# Stopwatch.net
KiCad netlist of a schematic drawn in EAGLE
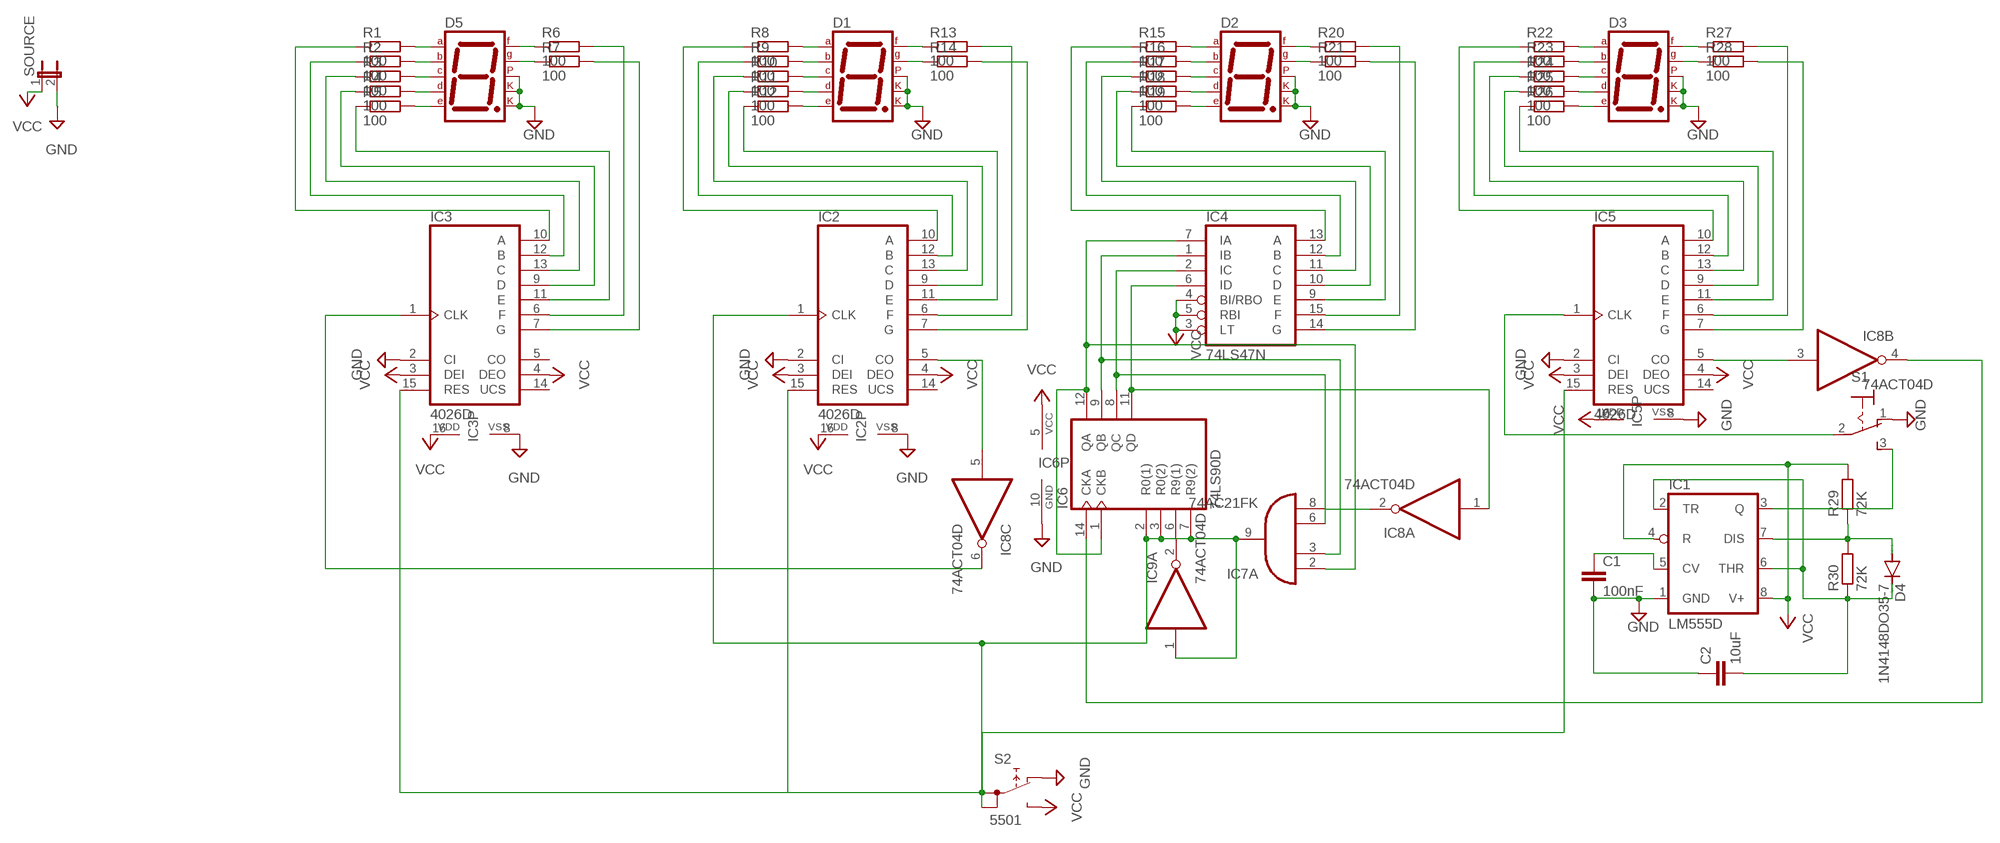
[diagram p0: schematic, sheet 1]

(export (version "E")
  (design (tool "Eeschema 10.0.6"))
  (components
    (comp (ref "C1")
      (value "100nF")
      (footprint "eagle-import:C2.5-2")
      (libsource (lib "eagle-import") (part "C2.5/2"))
    )
    (comp (ref "C2")
      (value "10uF")
      (footprint "eagle-import:C2.5-2")
      (libsource (lib "eagle-import") (part "C2.5/2"))
    )
    (comp (ref "D1")
      (value "7SEG-CK")
      (footprint "eagle-import:7SEG-13")
      (libsource (lib "eagle-import") (part "7SEG-CK"))
    )
    (comp (ref "D2")
      (value "7SEG-CK")
      (footprint "eagle-import:7SEG-13")
      (libsource (lib "eagle-import") (part "7SEG-CK"))
    )
    (comp (ref "D3")
      (value "7SEG-CK")
      (footprint "eagle-import:7SEG-13")
      (libsource (lib "eagle-import") (part "7SEG-CK"))
    )
    (comp (ref "D4")
      (value "1N4148DO35-7")
      (footprint "eagle-import:DO35-7")
      (libsource (lib "eagle-import") (part "1N4148DO35-7"))
    )
    (comp (ref "D5")
      (value "7SEG-CK")
      (footprint "eagle-import:7SEG-13")
      (libsource (lib "eagle-import") (part "7SEG-CK"))
    )
    (comp (ref "IC1")
      (value "LM555D")
      (footprint "eagle-import:SO08")
      (libsource (lib "eagle-import") (part "555DLM"))
    )
    (comp (ref "IC2")
      (value "4026D")
      (footprint "eagle-import:SO16")
      (libsource (lib "eagle-import") (part "4026D"))
    )
    (comp (ref "IC3")
      (value "4026D")
      (footprint "eagle-import:SO16")
      (libsource (lib "eagle-import") (part "4026D"))
    )
    (comp (ref "IC4")
      (value "74LS47N")
      (footprint "eagle-import:DIL16")
      (libsource (lib "eagle-import") (part "7447NLS"))
    )
    (comp (ref "IC5")
      (value "4026D")
      (footprint "eagle-import:SO16")
      (libsource (lib "eagle-import") (part "4026D"))
    )
    (comp (ref "IC6")
      (value "74LS90D")
      (footprint "eagle-import:SO14")
      (libsource (lib "eagle-import") (part "7490DLS"))
    )
    (comp (ref "IC7")
      (value "74AC21FK")
      (footprint "eagle-import:LCC20")
      (libsource (lib "eagle-import") (part "7421FKAC"))
    )
    (comp (ref "IC8")
      (value "74ACT04D")
      (footprint "eagle-import:SO14")
      (libsource (lib "eagle-import") (part "7404DACT"))
    )
    (comp (ref "IC9")
      (value "74ACT04D")
      (footprint "eagle-import:SO14")
      (libsource (lib "eagle-import") (part "7404DACT"))
    )
    (comp (ref "R1")
      (value "100")
      (footprint "eagle-import:R0805")
      (libsource (lib "eagle-import") (part "R-EU_R0805"))
    )
    (comp (ref "R2")
      (value "100")
      (footprint "eagle-import:R0805")
      (libsource (lib "eagle-import") (part "R-EU_R0805"))
    )
    (comp (ref "R3")
      (value "100")
      (footprint "eagle-import:R0805")
      (libsource (lib "eagle-import") (part "R-EU_R0805"))
    )
    (comp (ref "R4")
      (value "100")
      (footprint "eagle-import:R0805")
      (libsource (lib "eagle-import") (part "R-EU_R0805"))
    )
    (comp (ref "R5")
      (value "100")
      (footprint "eagle-import:R0805")
      (libsource (lib "eagle-import") (part "R-EU_R0805"))
    )
    (comp (ref "R6")
      (value "100")
      (footprint "eagle-import:R0805")
      (libsource (lib "eagle-import") (part "R-EU_R0805"))
    )
    (comp (ref "R7")
      (value "100")
      (footprint "eagle-import:R0805")
      (libsource (lib "eagle-import") (part "R-EU_R0805"))
    )
    (comp (ref "R8")
      (value "100")
      (footprint "eagle-import:R0805")
      (libsource (lib "eagle-import") (part "R-EU_R0805"))
    )
    (comp (ref "R9")
      (value "100")
      (footprint "eagle-import:R0805")
      (libsource (lib "eagle-import") (part "R-EU_R0805"))
    )
    (comp (ref "R10")
      (value "100")
      (footprint "eagle-import:R0805")
      (libsource (lib "eagle-import") (part "R-EU_R0805"))
    )
    (comp (ref "R11")
      (value "100")
      (footprint "eagle-import:R0805")
      (libsource (lib "eagle-import") (part "R-EU_R0805"))
    )
    (comp (ref "R12")
      (value "100")
      (footprint "eagle-import:R0805")
      (libsource (lib "eagle-import") (part "R-EU_R0805"))
    )
    (comp (ref "R13")
      (value "100")
      (footprint "eagle-import:R0805")
      (libsource (lib "eagle-import") (part "R-EU_R0805"))
    )
    (comp (ref "R14")
      (value "100")
      (footprint "eagle-import:R0805")
      (libsource (lib "eagle-import") (part "R-EU_R0805"))
    )
    (comp (ref "R15")
      (value "100")
      (footprint "eagle-import:R0805")
      (libsource (lib "eagle-import") (part "R-EU_R0805"))
    )
    (comp (ref "R16")
      (value "100")
      (footprint "eagle-import:R0805")
      (libsource (lib "eagle-import") (part "R-EU_R0805"))
    )
    (comp (ref "R17")
      (value "100")
      (footprint "eagle-import:R0805")
      (libsource (lib "eagle-import") (part "R-EU_R0805"))
    )
    (comp (ref "R18")
      (value "100")
      (footprint "eagle-import:R0805")
      (libsource (lib "eagle-import") (part "R-EU_R0805"))
    )
    (comp (ref "R19")
      (value "100")
      (footprint "eagle-import:R0805")
      (libsource (lib "eagle-import") (part "R-EU_R0805"))
    )
    (comp (ref "R20")
      (value "100")
      (footprint "eagle-import:R0805")
      (libsource (lib "eagle-import") (part "R-EU_R0805"))
    )
    (comp (ref "R21")
      (value "100")
      (footprint "eagle-import:R0805")
      (libsource (lib "eagle-import") (part "R-EU_R0805"))
    )
    (comp (ref "R22")
      (value "100")
      (footprint "eagle-import:R0805")
      (libsource (lib "eagle-import") (part "R-EU_R0805"))
    )
    (comp (ref "R23")
      (value "100")
      (footprint "eagle-import:R0805")
      (libsource (lib "eagle-import") (part "R-EU_R0805"))
    )
    (comp (ref "R24")
      (value "100")
      (footprint "eagle-import:R0805")
      (libsource (lib "eagle-import") (part "R-EU_R0805"))
    )
    (comp (ref "R25")
      (value "100")
      (footprint "eagle-import:R0805")
      (libsource (lib "eagle-import") (part "R-EU_R0805"))
    )
    (comp (ref "R26")
      (value "100")
      (footprint "eagle-import:R0805")
      (libsource (lib "eagle-import") (part "R-EU_R0805"))
    )
    (comp (ref "R27")
      (value "100")
      (footprint "eagle-import:R0805")
      (libsource (lib "eagle-import") (part "R-EU_R0805"))
    )
    (comp (ref "R28")
      (value "100")
      (footprint "eagle-import:R0805")
      (libsource (lib "eagle-import") (part "R-EU_R0805"))
    )
    (comp (ref "R29")
      (value "72K")
      (footprint "eagle-import:R0805")
      (libsource (lib "eagle-import") (part "R-EU_R0805"))
    )
    (comp (ref "R30")
      (value "72K")
      (footprint "eagle-import:R0805")
      (libsource (lib "eagle-import") (part "R-EU_R0805"))
    )
    (comp (ref "S1")
      (value "320-916")
      (footprint "eagle-import:320-916")
      (libsource (lib "eagle-import") (part "320-916"))
    )
    (comp (ref "S2")
      (value "5501")
      (footprint "eagle-import:5501")
      (libsource (lib "eagle-import") (part "55?01"))
    )
    (comp (ref "SOURCE")
      (value "JP1E")
      (footprint "eagle-import:JP1")
      (libsource (lib "eagle-import") (part "JP1E"))
    )
  )
  (nets
    (net (code "1") (name "GND") (class "Default")
      (node (ref "C1") (pin "2") (pinfunction "2_2") (pintype "passive"))
      (node (ref "C2") (pin "1") (pinfunction "1_1") (pintype "passive"))
      (node (ref "D1") (pin "3") (pinfunction "CK1_3") (pintype "passive"))
      (node (ref "D1") (pin "5") (pinfunction "DP_5") (pintype "passive"))
      (node (ref "D1") (pin "8") (pinfunction "CK2_8") (pintype "passive"))
      (node (ref "D2") (pin "3") (pinfunction "CK1_3") (pintype "passive"))
      (node (ref "D2") (pin "5") (pinfunction "DP_5") (pintype "passive"))
      (node (ref "D2") (pin "8") (pinfunction "CK2_8") (pintype "passive"))
      (node (ref "D3") (pin "3") (pinfunction "CK1_3") (pintype "passive"))
      (node (ref "D3") (pin "5") (pinfunction "DP_5") (pintype "passive"))
      (node (ref "D3") (pin "8") (pinfunction "CK2_8") (pintype "passive"))
      (node (ref "D5") (pin "3") (pinfunction "CK1_3") (pintype "passive"))
      (node (ref "D5") (pin "5") (pinfunction "DP_5") (pintype "passive"))
      (node (ref "D5") (pin "8") (pinfunction "CK2_8") (pintype "passive"))
      (node (ref "IC1") (pin "1") (pinfunction "GND_1") (pintype "power_in"))
      (node (ref "IC2") (pin "2") (pinfunction "CI_2") (pintype "input"))
      (node (ref "IC2") (pin "8") (pinfunction "VSS_8") (pintype "power_in"))
      (node (ref "IC3") (pin "2") (pinfunction "CI_2") (pintype "input"))
      (node (ref "IC3") (pin "8") (pinfunction "VSS_8") (pintype "power_in"))
      (node (ref "IC5") (pin "2") (pinfunction "CI_2") (pintype "input"))
      (node (ref "IC5") (pin "8") (pinfunction "VSS_8") (pintype "power_in"))
      (node (ref "IC6") (pin "10") (pinfunction "GND_10") (pintype "power_in"))
      (node (ref "S1") (pin "1") (pinfunction "O_1") (pintype "passive"))
      (node (ref "S2") (pin "NC") (pinfunction "NC_NC") (pintype "passive"))
      (node (ref "SOURCE") (pin "2") (pinfunction "2_2") (pintype "passive"))
    )
    (net (code "2") (name "Net-(D1-A)") (class "Default")
      (node (ref "D1") (pin "7") (pinfunction "A_7") (pintype "passive"))
      (node (ref "R8") (pin "2") (pinfunction "2_2") (pintype "passive"))
    )
    (net (code "3") (name "Net-(D1-B)") (class "Default")
      (node (ref "D1") (pin "6") (pinfunction "B_6") (pintype "passive"))
      (node (ref "R9") (pin "2") (pinfunction "2_2") (pintype "passive"))
    )
    (net (code "4") (name "Net-(D1-C)") (class "Default")
      (node (ref "D1") (pin "4") (pinfunction "C_4") (pintype "passive"))
      (node (ref "R10") (pin "2") (pinfunction "2_2") (pintype "passive"))
    )
    (net (code "5") (name "Net-(D1-D)") (class "Default")
      (node (ref "D1") (pin "2") (pinfunction "D_2") (pintype "passive"))
      (node (ref "R11") (pin "2") (pinfunction "2_2") (pintype "passive"))
    )
    (net (code "6") (name "Net-(D1-E)") (class "Default")
      (node (ref "D1") (pin "1") (pinfunction "E_1") (pintype "passive"))
      (node (ref "R12") (pin "2") (pinfunction "2_2") (pintype "passive"))
    )
    (net (code "7") (name "Net-(D1-F)") (class "Default")
      (node (ref "D1") (pin "9") (pinfunction "F_9") (pintype "passive"))
      (node (ref "R13") (pin "1") (pinfunction "1_1") (pintype "passive"))
    )
    (net (code "8") (name "Net-(D1-G)") (class "Default")
      (node (ref "D1") (pin "10") (pinfunction "G_10") (pintype "passive"))
      (node (ref "R14") (pin "1") (pinfunction "1_1") (pintype "passive"))
    )
    (net (code "9") (name "Net-(D2-A)") (class "Default")
      (node (ref "D2") (pin "7") (pinfunction "A_7") (pintype "passive"))
      (node (ref "R15") (pin "2") (pinfunction "2_2") (pintype "passive"))
    )
    (net (code "10") (name "Net-(D2-B)") (class "Default")
      (node (ref "D2") (pin "6") (pinfunction "B_6") (pintype "passive"))
      (node (ref "R16") (pin "2") (pinfunction "2_2") (pintype "passive"))
    )
    (net (code "11") (name "Net-(D2-C)") (class "Default")
      (node (ref "D2") (pin "4") (pinfunction "C_4") (pintype "passive"))
      (node (ref "R17") (pin "2") (pinfunction "2_2") (pintype "passive"))
    )
    (net (code "12") (name "Net-(D2-D)") (class "Default")
      (node (ref "D2") (pin "2") (pinfunction "D_2") (pintype "passive"))
      (node (ref "R18") (pin "2") (pinfunction "2_2") (pintype "passive"))
    )
    (net (code "13") (name "Net-(D2-E)") (class "Default")
      (node (ref "D2") (pin "1") (pinfunction "E_1") (pintype "passive"))
      (node (ref "R19") (pin "2") (pinfunction "2_2") (pintype "passive"))
    )
    (net (code "14") (name "Net-(D2-F)") (class "Default")
      (node (ref "D2") (pin "9") (pinfunction "F_9") (pintype "passive"))
      (node (ref "R20") (pin "1") (pinfunction "1_1") (pintype "passive"))
    )
    (net (code "15") (name "Net-(D2-G)") (class "Default")
      (node (ref "D2") (pin "10") (pinfunction "G_10") (pintype "passive"))
      (node (ref "R21") (pin "1") (pinfunction "1_1") (pintype "passive"))
    )
    (net (code "16") (name "Net-(D3-A)") (class "Default")
      (node (ref "D3") (pin "7") (pinfunction "A_7") (pintype "passive"))
      (node (ref "R22") (pin "2") (pinfunction "2_2") (pintype "passive"))
    )
    (net (code "17") (name "Net-(D3-B)") (class "Default")
      (node (ref "D3") (pin "6") (pinfunction "B_6") (pintype "passive"))
      (node (ref "R23") (pin "2") (pinfunction "2_2") (pintype "passive"))
    )
    (net (code "18") (name "Net-(D3-C)") (class "Default")
      (node (ref "D3") (pin "4") (pinfunction "C_4") (pintype "passive"))
      (node (ref "R24") (pin "2") (pinfunction "2_2") (pintype "passive"))
    )
    (net (code "19") (name "Net-(D3-D)") (class "Default")
      (node (ref "D3") (pin "2") (pinfunction "D_2") (pintype "passive"))
      (node (ref "R25") (pin "2") (pinfunction "2_2") (pintype "passive"))
    )
    (net (code "20") (name "Net-(D3-E)") (class "Default")
      (node (ref "D3") (pin "1") (pinfunction "E_1") (pintype "passive"))
      (node (ref "R26") (pin "2") (pinfunction "2_2") (pintype "passive"))
    )
    (net (code "21") (name "Net-(D3-F)") (class "Default")
      (node (ref "D3") (pin "9") (pinfunction "F_9") (pintype "passive"))
      (node (ref "R27") (pin "1") (pinfunction "1_1") (pintype "passive"))
    )
    (net (code "22") (name "Net-(D3-G)") (class "Default")
      (node (ref "D3") (pin "10") (pinfunction "G_10") (pintype "passive"))
      (node (ref "R28") (pin "1") (pinfunction "1_1") (pintype "passive"))
    )
    (net (code "23") (name "Net-(D5-A)") (class "Default")
      (node (ref "D5") (pin "7") (pinfunction "A_7") (pintype "passive"))
      (node (ref "R1") (pin "2") (pinfunction "2_2") (pintype "passive"))
    )
    (net (code "24") (name "Net-(D5-B)") (class "Default")
      (node (ref "D5") (pin "6") (pinfunction "B_6") (pintype "passive"))
      (node (ref "R2") (pin "2") (pinfunction "2_2") (pintype "passive"))
    )
    (net (code "25") (name "Net-(D5-C)") (class "Default")
      (node (ref "D5") (pin "4") (pinfunction "C_4") (pintype "passive"))
      (node (ref "R3") (pin "2") (pinfunction "2_2") (pintype "passive"))
    )
    (net (code "26") (name "Net-(D5-D)") (class "Default")
      (node (ref "D5") (pin "2") (pinfunction "D_2") (pintype "passive"))
      (node (ref "R4") (pin "2") (pinfunction "2_2") (pintype "passive"))
    )
    (net (code "27") (name "Net-(D5-E)") (class "Default")
      (node (ref "D5") (pin "1") (pinfunction "E_1") (pintype "passive"))
      (node (ref "R5") (pin "2") (pinfunction "2_2") (pintype "passive"))
    )
    (net (code "28") (name "Net-(D5-F)") (class "Default")
      (node (ref "D5") (pin "9") (pinfunction "F_9") (pintype "passive"))
      (node (ref "R6") (pin "1") (pinfunction "1_1") (pintype "passive"))
    )
    (net (code "29") (name "Net-(D5-G)") (class "Default")
      (node (ref "D5") (pin "10") (pinfunction "G_10") (pintype "passive"))
      (node (ref "R7") (pin "1") (pinfunction "1_1") (pintype "passive"))
    )
    (net (code "30") (name "Net-(IC1-CV)") (class "Default")
      (node (ref "C1") (pin "1") (pinfunction "1_1") (pintype "passive"))
      (node (ref "IC1") (pin "5") (pinfunction "CV_5") (pintype "input"))
    )
    (net (code "31") (name "Net-(IC1-DIS)") (class "Default")
      (node (ref "D4") (pin "A") (pinfunction "A_A") (pintype "passive"))
      (node (ref "IC1") (pin "7") (pinfunction "DIS_7") (pintype "input"))
      (node (ref "R29") (pin "1") (pinfunction "1_1") (pintype "passive"))
      (node (ref "R30") (pin "2") (pinfunction "2_2") (pintype "passive"))
    )
    (net (code "32") (name "Net-(IC1-Q)") (class "Default")
      (node (ref "IC1") (pin "3") (pinfunction "Q_3") (pintype "output"))
      (node (ref "S1") (pin "3") (pinfunction "S_3") (pintype "passive"))
    )
    (net (code "33") (name "Net-(IC1-THR)") (class "Default")
      (node (ref "C2") (pin "2") (pinfunction "2_2") (pintype "passive"))
      (node (ref "D4") (pin "C") (pinfunction "C_C") (pintype "passive"))
      (node (ref "IC1") (pin "2") (pinfunction "TR_2") (pintype "input"))
      (node (ref "IC1") (pin "6") (pinfunction "THR_6") (pintype "input"))
      (node (ref "R30") (pin "1") (pinfunction "1_1") (pintype "passive"))
    )
    (net (code "34") (name "Net-(IC2A-A)") (class "Default")
      (node (ref "IC2") (pin "10") (pinfunction "A_10") (pintype "output"))
      (node (ref "R8") (pin "1") (pinfunction "1_1") (pintype "passive"))
    )
    (net (code "35") (name "Net-(IC2A-B)") (class "Default")
      (node (ref "IC2") (pin "12") (pinfunction "B_12") (pintype "output"))
      (node (ref "R9") (pin "1") (pinfunction "1_1") (pintype "passive"))
    )
    (net (code "36") (name "Net-(IC2A-C)") (class "Default")
      (node (ref "IC2") (pin "13") (pinfunction "C_13") (pintype "output"))
      (node (ref "R10") (pin "1") (pinfunction "1_1") (pintype "passive"))
    )
    (net (code "37") (name "Net-(IC2A-CLK)") (class "Default")
      (node (ref "IC2") (pin "1") (pinfunction "CLK_1") (pintype "input"))
      (node (ref "IC2") (pin "15") (pinfunction "RES_15") (pintype "input"))
      (node (ref "IC3") (pin "15") (pinfunction "RES_15") (pintype "input"))
      (node (ref "IC5") (pin "15") (pinfunction "RES_15") (pintype "input"))
      (node (ref "IC6") (pin "2") (pinfunction "R0(1)_2") (pintype "input"))
      (node (ref "IC6") (pin "3") (pinfunction "R0(2)_3") (pintype "input"))
      (node (ref "IC6") (pin "7") (pinfunction "R9(2)_7") (pintype "input"))
      (node (ref "IC7") (pin "9") (pinfunction "O_9") (pintype "output"))
      (node (ref "IC9") (pin "1") (pinfunction "I_1") (pintype "input"))
      (node (ref "S2") (pin "1A") (pinfunction "1A_1A") (pintype "passive"))
      (node (ref "S2") (pin "1B") (pinfunction "1B_1B") (pintype "passive"))
    )
    (net (code "38") (name "Net-(IC2A-CO)") (class "Default")
      (node (ref "IC2") (pin "5") (pinfunction "CO_5") (pintype "output"))
      (node (ref "IC8") (pin "5") (pinfunction "I_5") (pintype "input"))
    )
    (net (code "39") (name "Net-(IC2A-D)") (class "Default")
      (node (ref "IC2") (pin "9") (pinfunction "D_9") (pintype "output"))
      (node (ref "R11") (pin "1") (pinfunction "1_1") (pintype "passive"))
    )
    (net (code "40") (name "Net-(IC2A-E)") (class "Default")
      (node (ref "IC2") (pin "11") (pinfunction "E_11") (pintype "output"))
      (node (ref "R12") (pin "1") (pinfunction "1_1") (pintype "passive"))
    )
    (net (code "41") (name "Net-(IC2A-F)") (class "Default")
      (node (ref "IC2") (pin "6") (pinfunction "F_6") (pintype "output"))
      (node (ref "R13") (pin "2") (pinfunction "2_2") (pintype "passive"))
    )
    (net (code "42") (name "Net-(IC2A-G)") (class "Default")
      (node (ref "IC2") (pin "7") (pinfunction "G_7") (pintype "output"))
      (node (ref "R14") (pin "2") (pinfunction "2_2") (pintype "passive"))
    )
    (net (code "43") (name "Net-(IC3A-A)") (class "Default")
      (node (ref "IC3") (pin "10") (pinfunction "A_10") (pintype "output"))
      (node (ref "R1") (pin "1") (pinfunction "1_1") (pintype "passive"))
    )
    (net (code "44") (name "Net-(IC3A-B)") (class "Default")
      (node (ref "IC3") (pin "12") (pinfunction "B_12") (pintype "output"))
      (node (ref "R2") (pin "1") (pinfunction "1_1") (pintype "passive"))
    )
    (net (code "45") (name "Net-(IC3A-C)") (class "Default")
      (node (ref "IC3") (pin "13") (pinfunction "C_13") (pintype "output"))
      (node (ref "R3") (pin "1") (pinfunction "1_1") (pintype "passive"))
    )
    (net (code "46") (name "Net-(IC3A-CLK)") (class "Default")
      (node (ref "IC3") (pin "1") (pinfunction "CLK_1") (pintype "input"))
      (node (ref "IC8") (pin "6") (pinfunction "O_6") (pintype "output"))
    )
    (net (code "47") (name "Net-(IC3A-D)") (class "Default")
      (node (ref "IC3") (pin "9") (pinfunction "D_9") (pintype "output"))
      (node (ref "R4") (pin "1") (pinfunction "1_1") (pintype "passive"))
    )
    (net (code "48") (name "Net-(IC3A-E)") (class "Default")
      (node (ref "IC3") (pin "11") (pinfunction "E_11") (pintype "output"))
      (node (ref "R5") (pin "1") (pinfunction "1_1") (pintype "passive"))
    )
    (net (code "49") (name "Net-(IC3A-F)") (class "Default")
      (node (ref "IC3") (pin "6") (pinfunction "F_6") (pintype "output"))
      (node (ref "R6") (pin "2") (pinfunction "2_2") (pintype "passive"))
    )
    (net (code "50") (name "Net-(IC3A-G)") (class "Default")
      (node (ref "IC3") (pin "7") (pinfunction "G_7") (pintype "output"))
      (node (ref "R7") (pin "2") (pinfunction "2_2") (pintype "passive"))
    )
    (net (code "51") (name "Net-(IC4A-A)") (class "Default")
      (node (ref "IC4") (pin "13") (pinfunction "A_13") (pintype "output"))
      (node (ref "R15") (pin "1") (pinfunction "1_1") (pintype "passive"))
    )
    (net (code "52") (name "Net-(IC4A-B)") (class "Default")
      (node (ref "IC4") (pin "12") (pinfunction "B_12") (pintype "output"))
      (node (ref "R16") (pin "1") (pinfunction "1_1") (pintype "passive"))
    )
    (net (code "53") (name "Net-(IC4A-C)") (class "Default")
      (node (ref "IC4") (pin "11") (pinfunction "C_11") (pintype "output"))
      (node (ref "R17") (pin "1") (pinfunction "1_1") (pintype "passive"))
    )
    (net (code "54") (name "Net-(IC4A-D)") (class "Default")
      (node (ref "IC4") (pin "10") (pinfunction "D_10") (pintype "output"))
      (node (ref "R18") (pin "1") (pinfunction "1_1") (pintype "passive"))
    )
    (net (code "55") (name "Net-(IC4A-E)") (class "Default")
      (node (ref "IC4") (pin "9") (pinfunction "E_9") (pintype "output"))
      (node (ref "R19") (pin "1") (pinfunction "1_1") (pintype "passive"))
    )
    (net (code "56") (name "Net-(IC4A-F)") (class "Default")
      (node (ref "IC4") (pin "15") (pinfunction "F_15") (pintype "output"))
      (node (ref "R20") (pin "2") (pinfunction "2_2") (pintype "passive"))
    )
    (net (code "57") (name "Net-(IC4A-G)") (class "Default")
      (node (ref "IC4") (pin "14") (pinfunction "G_14") (pintype "output"))
      (node (ref "R21") (pin "2") (pinfunction "2_2") (pintype "passive"))
    )
    (net (code "58") (name "Net-(IC4A-IA)") (class "Default")
      (node (ref "IC4") (pin "7") (pinfunction "IA_7") (pintype "input"))
      (node (ref "IC6") (pin "1") (pinfunction "CKB_1") (pintype "input"))
      (node (ref "IC6") (pin "12") (pinfunction "QA_12") (pintype "output"))
      (node (ref "IC7") (pin "2") (pinfunction "I0_2") (pintype "input"))
    )
    (net (code "59") (name "Net-(IC4A-IB)") (class "Default")
      (node (ref "IC4") (pin "1") (pinfunction "IB_1") (pintype "input"))
      (node (ref "IC6") (pin "9") (pinfunction "QB_9") (pintype "output"))
      (node (ref "IC7") (pin "3") (pinfunction "I1_3") (pintype "input"))
    )
    (net (code "60") (name "Net-(IC4A-IC)") (class "Default")
      (node (ref "IC4") (pin "2") (pinfunction "IC_2") (pintype "input"))
      (node (ref "IC6") (pin "8") (pinfunction "QC_8") (pintype "output"))
      (node (ref "IC7") (pin "6") (pinfunction "I2_6") (pintype "input"))
    )
    (net (code "61") (name "Net-(IC4A-ID)") (class "Default")
      (node (ref "IC4") (pin "6") (pinfunction "ID_6") (pintype "input"))
      (node (ref "IC6") (pin "11") (pinfunction "QD_11") (pintype "output"))
      (node (ref "IC8") (pin "1") (pinfunction "I_1") (pintype "input"))
    )
    (net (code "62") (name "Net-(IC5A-A)") (class "Default")
      (node (ref "IC5") (pin "10") (pinfunction "A_10") (pintype "output"))
      (node (ref "R22") (pin "1") (pinfunction "1_1") (pintype "passive"))
    )
    (net (code "63") (name "Net-(IC5A-B)") (class "Default")
      (node (ref "IC5") (pin "12") (pinfunction "B_12") (pintype "output"))
      (node (ref "R23") (pin "1") (pinfunction "1_1") (pintype "passive"))
    )
    (net (code "64") (name "Net-(IC5A-C)") (class "Default")
      (node (ref "IC5") (pin "13") (pinfunction "C_13") (pintype "output"))
      (node (ref "R24") (pin "1") (pinfunction "1_1") (pintype "passive"))
    )
    (net (code "65") (name "Net-(IC5A-CLK)") (class "Default")
      (node (ref "IC5") (pin "1") (pinfunction "CLK_1") (pintype "input"))
      (node (ref "S1") (pin "2") (pinfunction "P_2") (pintype "passive"))
    )
    (net (code "66") (name "Net-(IC5A-CO)") (class "Default")
      (node (ref "IC5") (pin "5") (pinfunction "CO_5") (pintype "output"))
      (node (ref "IC8") (pin "3") (pinfunction "I_3") (pintype "input"))
    )
    (net (code "67") (name "Net-(IC5A-D)") (class "Default")
      (node (ref "IC5") (pin "9") (pinfunction "D_9") (pintype "output"))
      (node (ref "R25") (pin "1") (pinfunction "1_1") (pintype "passive"))
    )
    (net (code "68") (name "Net-(IC5A-E)") (class "Default")
      (node (ref "IC5") (pin "11") (pinfunction "E_11") (pintype "output"))
      (node (ref "R26") (pin "1") (pinfunction "1_1") (pintype "passive"))
    )
    (net (code "69") (name "Net-(IC5A-F)") (class "Default")
      (node (ref "IC5") (pin "6") (pinfunction "F_6") (pintype "output"))
      (node (ref "R27") (pin "2") (pinfunction "2_2") (pintype "passive"))
    )
    (net (code "70") (name "Net-(IC5A-G)") (class "Default")
      (node (ref "IC5") (pin "7") (pinfunction "G_7") (pintype "output"))
      (node (ref "R28") (pin "2") (pinfunction "2_2") (pintype "passive"))
    )
    (net (code "71") (name "Net-(IC6A-CKA)") (class "Default")
      (node (ref "IC6") (pin "14") (pinfunction "CKA_14") (pintype "input"))
      (node (ref "IC8") (pin "4") (pinfunction "O_4") (pintype "output"))
    )
    (net (code "72") (name "Net-(IC6A-R9(1))") (class "Default")
      (node (ref "IC6") (pin "6") (pinfunction "R9(1)_6") (pintype "input"))
      (node (ref "IC9") (pin "2") (pinfunction "O_2") (pintype "output"))
    )
    (net (code "73") (name "Net-(IC7A-I3)") (class "Default")
      (node (ref "IC7") (pin "8") (pinfunction "I3_8") (pintype "input"))
      (node (ref "IC8") (pin "2") (pinfunction "O_2") (pintype "output"))
    )
    (net (code "74") (name "VCC") (class "Default")
      (node (ref "IC1") (pin "4") (pinfunction "R_4") (pintype "input"))
      (node (ref "IC1") (pin "8") (pinfunction "V+_8") (pintype "power_in"))
      (node (ref "IC2") (pin "16") (pinfunction "VDD_16") (pintype "power_in"))
      (node (ref "IC2") (pin "3") (pinfunction "DEI_3") (pintype "input"))
      (node (ref "IC2") (pin "4") (pinfunction "DEO_4") (pintype "output"))
      (node (ref "IC3") (pin "16") (pinfunction "VDD_16") (pintype "power_in"))
      (node (ref "IC3") (pin "3") (pinfunction "DEI_3") (pintype "input"))
      (node (ref "IC3") (pin "4") (pinfunction "DEO_4") (pintype "output"))
      (node (ref "IC4") (pin "3") (pinfunction "LT_3") (pintype "input"))
      (node (ref "IC4") (pin "4") (pinfunction "BI/RBO_4") (pintype "input"))
      (node (ref "IC4") (pin "5") (pinfunction "RBI_5") (pintype "input"))
      (node (ref "IC5") (pin "16") (pinfunction "VDD_16") (pintype "power_in"))
      (node (ref "IC5") (pin "3") (pinfunction "DEI_3") (pintype "input"))
      (node (ref "IC5") (pin "4") (pinfunction "DEO_4") (pintype "output"))
      (node (ref "IC6") (pin "5") (pinfunction "VCC_5") (pintype "power_in"))
      (node (ref "R29") (pin "2") (pinfunction "2_2") (pintype "passive"))
      (node (ref "S2") (pin "NO") (pinfunction "NO_NO") (pintype "passive"))
      (node (ref "SOURCE") (pin "1") (pinfunction "1_1") (pintype "passive"))
    )
    (net (code "75") (name "unconnected-(IC2A-UCS-Pad14)") (class "Default")
      (node (ref "IC2") (pin "14") (pinfunction "UCS_14") (pintype "output"))
    )
    (net (code "76") (name "unconnected-(IC3A-CO-Pad5)") (class "Default")
      (node (ref "IC3") (pin "5") (pinfunction "CO_5") (pintype "output"))
    )
    (net (code "77") (name "unconnected-(IC3A-UCS-Pad14)") (class "Default")
      (node (ref "IC3") (pin "14") (pinfunction "UCS_14") (pintype "output"))
    )
    (net (code "78") (name "unconnected-(IC5A-UCS-Pad14)") (class "Default")
      (node (ref "IC5") (pin "14") (pinfunction "UCS_14") (pintype "output"))
    )
  )
)
